# Timbre.net
KiCad netlist of a schematic drawn in EAGLE
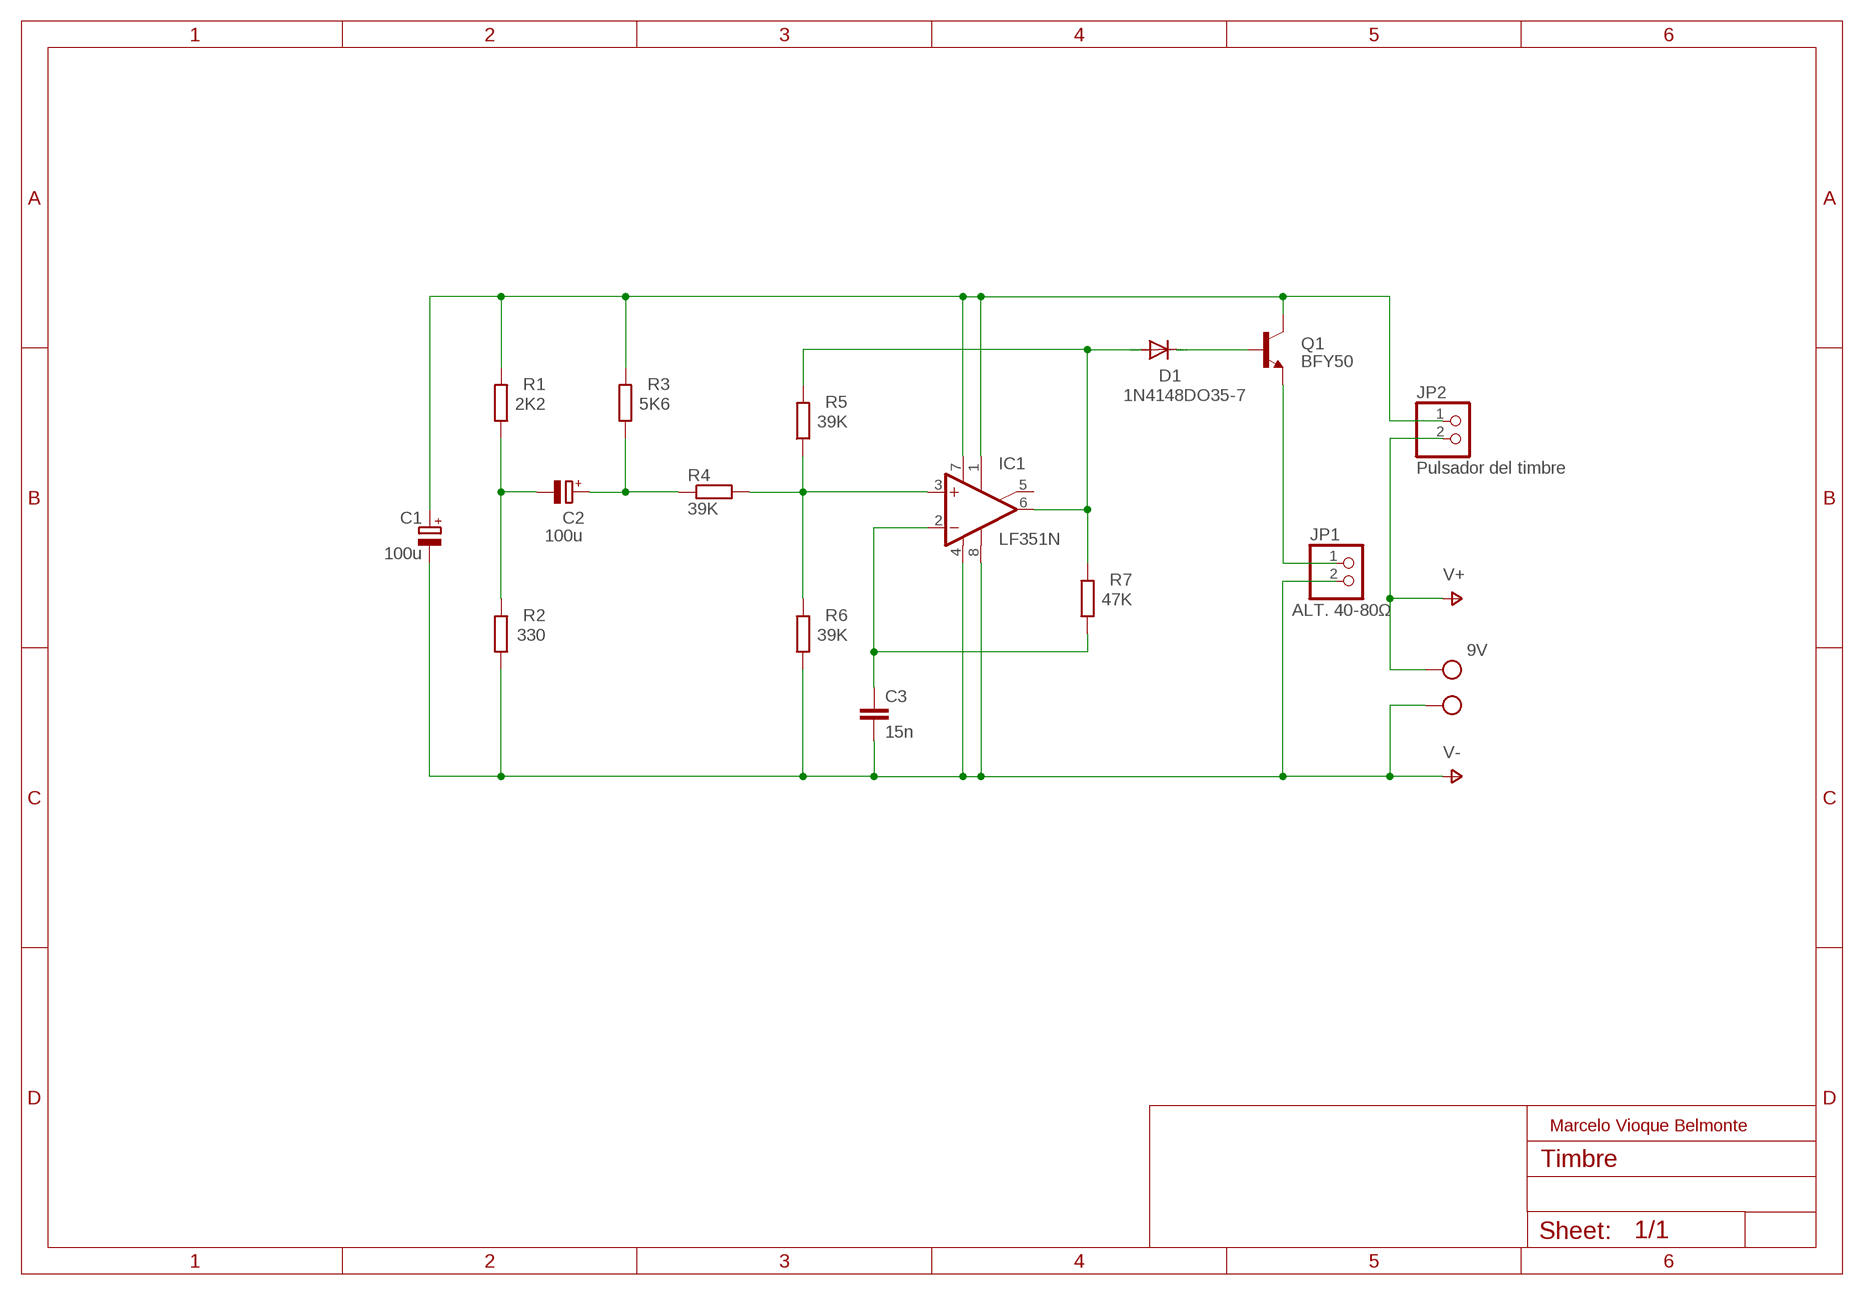
[diagram p0: schematic, sheet 1]

(export (version "E")
  (design (tool "Eeschema 10.0.6"))
  (components
    (comp (ref "C1")
      (value "100u")
      (footprint "eagle-import:E2,5-6")
      (libsource (lib "eagle-import") (part "CPOL-EUE2.5-6"))
    )
    (comp (ref "C2")
      (value "100u")
      (footprint "eagle-import:E2,5-6")
      (libsource (lib "eagle-import") (part "CPOL-EUE2.5-6"))
    )
    (comp (ref "C3")
      (value "15n")
      (footprint "eagle-import:C025_050-025X075")
      (libsource (lib "eagle-import") (part "C-EU025_050-025X075"))
    )
    (comp (ref "D1")
      (value "1N4148DO35-7")
      (footprint "eagle-import:DO35-7")
      (libsource (lib "eagle-import") (part "1N4148DO35-7"))
    )
    (comp (ref "IC1")
      (value "LF351N")
      (footprint "eagle-import:DIL08")
      (libsource (lib "eagle-import") (part "LF351N"))
    )
    (comp (ref "JP1")
      (value "ALT. 40-80Ω")
      (footprint "eagle-import:1X02")
      (libsource (lib "eagle-import") (part "PINHD-1X2"))
    )
    (comp (ref "JP2")
      (value "Pulsador del timbre")
      (footprint "eagle-import:1X02")
      (libsource (lib "eagle-import") (part "PINHD-1X2"))
    )
    (comp (ref "Q1")
      (value "BFY50")
      (footprint "eagle-import:TO39")
      (libsource (lib "eagle-import") (part "BFY50"))
    )
    (comp (ref "R1")
      (value "2K2")
      (footprint "eagle-import:0207_10")
      (libsource (lib "eagle-import") (part "R-EU_0207/10"))
    )
    (comp (ref "R2")
      (value "330")
      (footprint "eagle-import:0207_10")
      (libsource (lib "eagle-import") (part "R-EU_0207/10"))
    )
    (comp (ref "R3")
      (value "5K6")
      (footprint "eagle-import:0207_10")
      (libsource (lib "eagle-import") (part "R-EU_0207/10"))
    )
    (comp (ref "R4")
      (value "39K")
      (footprint "eagle-import:0207_10")
      (libsource (lib "eagle-import") (part "R-EU_0207/10"))
    )
    (comp (ref "R5")
      (value "39K")
      (footprint "eagle-import:0207_10")
      (libsource (lib "eagle-import") (part "R-EU_0207/10"))
    )
    (comp (ref "R6")
      (value "39K")
      (footprint "eagle-import:0207_10")
      (libsource (lib "eagle-import") (part "R-EU_0207/10"))
    )
    (comp (ref "R7")
      (value "47K")
      (footprint "eagle-import:0207_10")
      (libsource (lib "eagle-import") (part "R-EU_0207/10"))
    )
    (comp (ref "X1")
      (value "9V")
      (footprint "eagle-import:AK500_2")
      (libsource (lib "eagle-import") (part "AK500/2"))
    )
  )
  (nets
    (net (code "1") (name "Net-(C2-Pad+)") (class "Default")
      (node (ref "C2") (pin "+") (pinfunction "+_+") (pintype "passive"))
      (node (ref "R3") (pin "1") (pinfunction "1_1") (pintype "passive"))
      (node (ref "R4") (pin "1") (pinfunction "1_1") (pintype "passive"))
    )
    (net (code "2") (name "Net-(C2-Pad-)") (class "Default")
      (node (ref "C2") (pin "-") (pinfunction "-_-") (pintype "passive"))
      (node (ref "R1") (pin "1") (pinfunction "1_1") (pintype "passive"))
      (node (ref "R2") (pin "2") (pinfunction "2_2") (pintype "passive"))
    )
    (net (code "3") (name "Net-(IC1-+IN)") (class "Default")
      (node (ref "IC1") (pin "3") (pinfunction "+IN_3") (pintype "input"))
      (node (ref "R4") (pin "2") (pinfunction "2_2") (pintype "passive"))
      (node (ref "R5") (pin "1") (pinfunction "1_1") (pintype "passive"))
      (node (ref "R6") (pin "2") (pinfunction "2_2") (pintype "passive"))
    )
    (net (code "4") (name "Net-(IC1--IN)") (class "Default")
      (node (ref "C3") (pin "1") (pinfunction "1_1") (pintype "passive"))
      (node (ref "IC1") (pin "2") (pinfunction "-IN_2") (pintype "input"))
      (node (ref "R7") (pin "1") (pinfunction "1_1") (pintype "passive"))
    )
    (net (code "5") (name "Net-(IC1-ON1)") (class "Default")
      (node (ref "C1") (pin "+") (pinfunction "+_+") (pintype "passive"))
      (node (ref "IC1") (pin "1") (pinfunction "ON1_1") (pintype "passive"))
      (node (ref "IC1") (pin "7") (pinfunction "V+_7") (pintype "power_in"))
      (node (ref "JP2") (pin "1") (pinfunction "1_1") (pintype "passive"))
      (node (ref "Q1") (pin "3") (pinfunction "C_3") (pintype "passive"))
      (node (ref "R1") (pin "2") (pinfunction "2_2") (pintype "passive"))
      (node (ref "R3") (pin "2") (pinfunction "2_2") (pintype "passive"))
    )
    (net (code "6") (name "Net-(IC1-OUT)") (class "Default")
      (node (ref "D1") (pin "A") (pinfunction "A_A") (pintype "passive"))
      (node (ref "IC1") (pin "6") (pinfunction "OUT_6") (pintype "output"))
      (node (ref "R5") (pin "2") (pinfunction "2_2") (pintype "passive"))
      (node (ref "R7") (pin "2") (pinfunction "2_2") (pintype "passive"))
    )
    (net (code "7") (name "Net-(Q1-B)") (class "Default")
      (node (ref "D1") (pin "C") (pinfunction "C_C") (pintype "passive"))
      (node (ref "Q1") (pin "2") (pinfunction "B_2") (pintype "passive"))
    )
    (net (code "8") (name "Net-(Q1-E)") (class "Default")
      (node (ref "JP1") (pin "1") (pinfunction "1_1") (pintype "passive"))
      (node (ref "Q1") (pin "1") (pinfunction "E_1") (pintype "passive"))
    )
    (net (code "9") (name "V+") (class "Default")
      (node (ref "JP2") (pin "2") (pinfunction "2_2") (pintype "passive"))
      (node (ref "X1") (pin "2") (pinfunction "KL_2") (pintype "passive"))
    )
    (net (code "10") (name "V-") (class "Default")
      (node (ref "C1") (pin "-") (pinfunction "-_-") (pintype "passive"))
      (node (ref "C3") (pin "2") (pinfunction "2_2") (pintype "passive"))
      (node (ref "IC1") (pin "4") (pinfunction "V-_4") (pintype "power_in"))
      (node (ref "IC1") (pin "8") (pinfunction "OPT_8") (pintype "passive"))
      (node (ref "JP1") (pin "2") (pinfunction "2_2") (pintype "passive"))
      (node (ref "R2") (pin "1") (pinfunction "1_1") (pintype "passive"))
      (node (ref "R6") (pin "1") (pinfunction "1_1") (pintype "passive"))
      (node (ref "X1") (pin "1") (pinfunction "KL_1") (pintype "passive"))
    )
    (net (code "11") (name "unconnected-(IC1-ON2-Pad5)") (class "Default")
      (node (ref "IC1") (pin "5") (pinfunction "ON2_5") (pintype "passive"))
    )
  )
)
